# Moo_it.net
KiCad netlist of a schematic drawn in Altium Designer
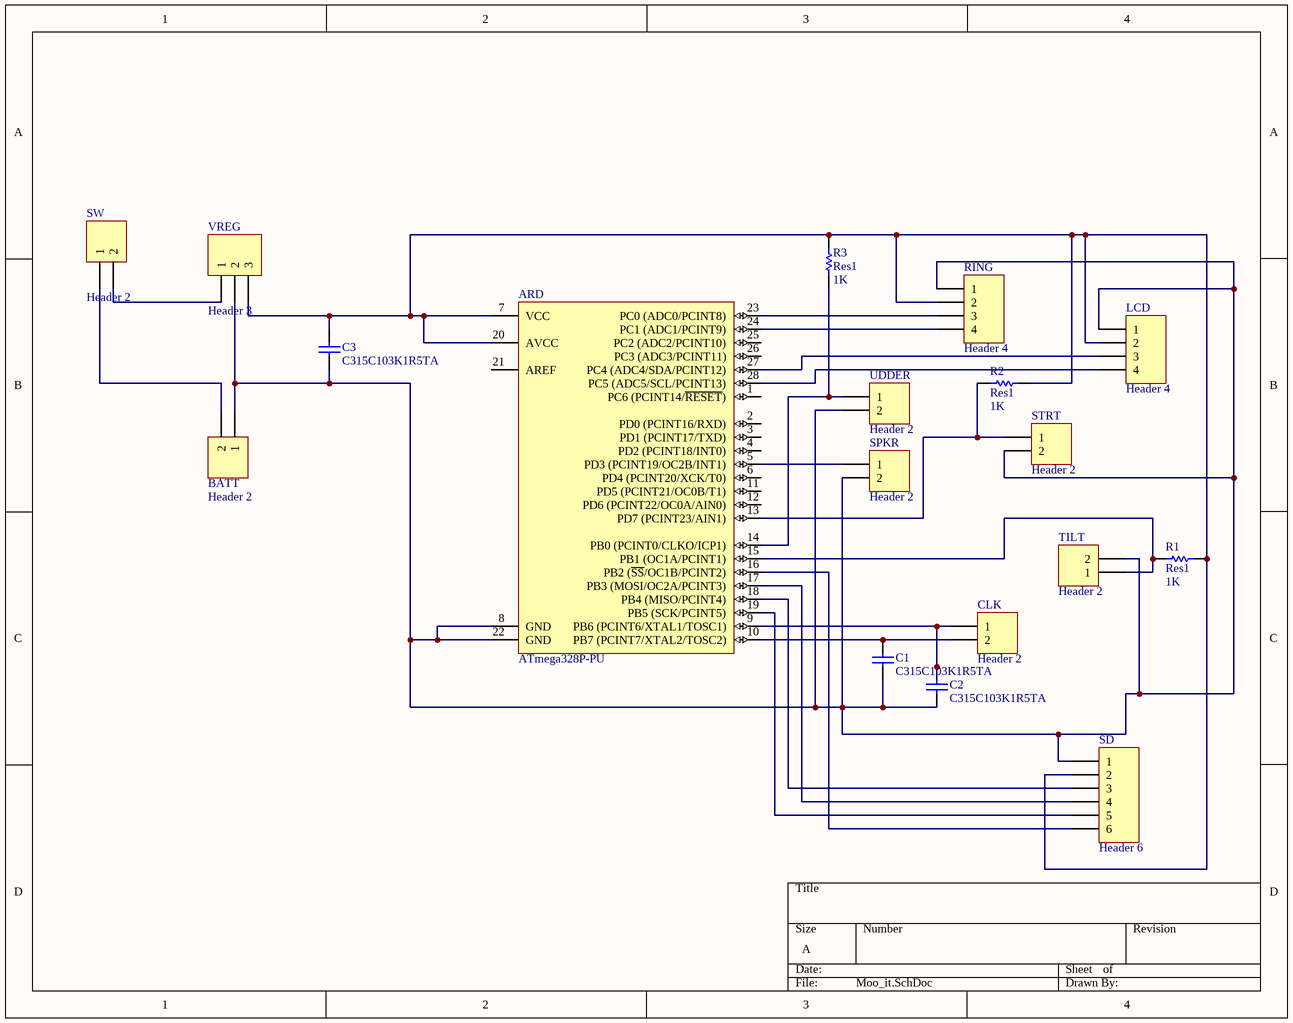
[diagram p0: Moo_it.SchDoc]

(export (version "E")
  (design (tool "Eeschema 10.0.6"))
  (components
    (comp (ref "ARD")
      (value "ATmega328P-PU")
      (footprint "28P3")
      (libsource (lib "Altium Content Vault") (part "MC-8B-ATM48-IL28"))
    )
    (comp (ref "BATT")
      (value "Header 2")
      (footprint "HDR1X2")
      (description "Header, 2-Pin")
      (fields (field (name "PUBLISHER") "Altium Limited"))
      (libsource (lib "") (part "Header 2_1"))
    )
    (comp (ref "C1")
      (value "C315C103K1R5TA")
      (footprint "KEMT-C315-THT-2")
      (description "Capacitor, Ceramic, 0.01 uF, +/- 10%, 100 V, X7R, -55 to 125 degC, 2-Pin THD, RoHS, Bulk")
      (libsource (lib "Altium Content Vault") (part "CAP-NP-2"))
    )
    (comp (ref "C2")
      (value "C315C103K1R5TA")
      (footprint "KEMT-C315-THT-2")
      (description "Capacitor, Ceramic, 0.01 uF, +/- 10%, 100 V, X7R, -55 to 125 degC, 2-Pin THD, RoHS, Bulk")
      (libsource (lib "Altium Content Vault") (part "CAP-NP-2"))
    )
    (comp (ref "C3")
      (value "C315C103K1R5TA")
      (footprint "KEMT-C315-THT-2")
      (description "Capacitor, Ceramic, 0.01 uF, +/- 10%, 100 V, X7R, -55 to 125 degC, 2-Pin THD, RoHS, Bulk")
      (libsource (lib "Altium Content Vault") (part "CAP-NP-2"))
    )
    (comp (ref "CLK")
      (value "Header 2")
      (footprint "HDR1X2")
      (description "Header, 2-Pin")
      (fields (field (name "PUBLISHER") "Altium Limited"))
      (libsource (lib "Miscellaneous Connectors") (part "Header 2"))
    )
    (comp (ref "LCD")
      (value "Header 4")
      (footprint "HDR1X4")
      (description "Header, 4-Pin")
      (fields (field (name "PUBLISHER") "Altium Limited"))
      (libsource (lib "Miscellaneous Connectors") (part "Header 4"))
    )
    (comp (ref "R1")
      (value "Res1")
      (footprint "AXIAL-0.3")
      (description "Resistor")
      (fields (field (name "ALTIUM_VALUE") "1K") (field (name "PUBLISHER") "Altium Limited"))
      (libsource (lib "Miscellaneous Devices") (part "Res1"))
    )
    (comp (ref "R2")
      (value "Res1")
      (footprint "AXIAL-0.3")
      (description "Resistor")
      (fields (field (name "ALTIUM_VALUE") "1K") (field (name "PUBLISHER") "Altium Limited"))
      (libsource (lib "Miscellaneous Devices") (part "Res1"))
    )
    (comp (ref "R3")
      (value "Res1")
      (footprint "AXIAL-0.3")
      (description "Resistor")
      (fields (field (name "ALTIUM_VALUE") "1K") (field (name "PUBLISHER") "Altium Limited"))
      (libsource (lib "Miscellaneous Devices") (part "Res1"))
    )
    (comp (ref "RING")
      (value "Header 4")
      (footprint "HDR1X4")
      (description "Header, 4-Pin")
      (fields (field (name "PUBLISHER") "Altium Limited"))
      (libsource (lib "Miscellaneous Connectors") (part "Header 4"))
    )
    (comp (ref "SD")
      (value "Header 6")
      (footprint "HDR1X6")
      (description "Header, 6-Pin")
      (fields (field (name "PUBLISHER") "Altium Limited"))
      (libsource (lib "Miscellaneous Connectors") (part "Header 6"))
    )
    (comp (ref "SPKR")
      (value "Header 2")
      (footprint "HDR1X2")
      (description "Header, 2-Pin")
      (fields (field (name "PUBLISHER") "Altium Limited"))
      (libsource (lib "Miscellaneous Connectors") (part "Header 2"))
    )
    (comp (ref "STRT")
      (value "Header 2")
      (footprint "HDR1X2")
      (description "Header, 2-Pin")
      (fields (field (name "PUBLISHER") "Altium Limited"))
      (libsource (lib "Miscellaneous Connectors") (part "Header 2"))
    )
    (comp (ref "SW")
      (value "Header 2")
      (footprint "HDR1X2")
      (description "Header, 2-Pin")
      (fields (field (name "PUBLISHER") "Altium Limited"))
      (libsource (lib "") (part "Header 2_2"))
    )
    (comp (ref "TILT")
      (value "Header 2")
      (footprint "HDR1X2")
      (description "Header, 2-Pin")
      (fields (field (name "PUBLISHER") "Altium Limited"))
      (libsource (lib "") (part "Header 2_3"))
    )
    (comp (ref "UDDER")
      (value "Header 2")
      (footprint "HDR1X2")
      (description "Header, 2-Pin")
      (fields (field (name "PUBLISHER") "Altium Limited"))
      (libsource (lib "Miscellaneous Connectors") (part "Header 2"))
    )
    (comp (ref "VREG")
      (value "Header 3")
      (footprint "HDR1X3")
      (description "Header, 3-Pin")
      (fields (field (name "PUBLISHER") "Altium Limited"))
      (libsource (lib "Miscellaneous Connectors") (part "Header 3"))
    )
  )
  (nets
    (net (code "1") (name "Net-(ARD-AVCC)") (class "Default")
      (node (ref "ARD") (pin "20") (pinfunction "AVCC_20") (pintype "power_in"))
      (node (ref "ARD") (pin "7") (pinfunction "VCC_7") (pintype "power_in"))
      (node (ref "C3") (pin "2") (pinfunction "2_2") (pintype "passive"))
      (node (ref "LCD") (pin "2") (pinfunction "2_2") (pintype "passive"))
      (node (ref "R1") (pin "2") (pinfunction "2_2") (pintype "passive"))
      (node (ref "R2") (pin "2") (pinfunction "2_2") (pintype "passive"))
      (node (ref "R3") (pin "2") (pinfunction "2_2") (pintype "passive"))
      (node (ref "RING") (pin "2") (pinfunction "2_2") (pintype "passive"))
      (node (ref "SD") (pin "2") (pinfunction "2_2") (pintype "passive"))
      (node (ref "VREG") (pin "3") (pinfunction "3_3") (pintype "passive"))
    )
    (net (code "2") (name "Net-(ARD-GND-Pad22)") (class "Default")
      (node (ref "ARD") (pin "22") (pinfunction "GND_22") (pintype "power_in"))
      (node (ref "ARD") (pin "8") (pinfunction "GND_8") (pintype "power_in"))
      (node (ref "BATT") (pin "1") (pinfunction "1_1") (pintype "passive"))
      (node (ref "C1") (pin "1") (pinfunction "1_1") (pintype "passive"))
      (node (ref "C2") (pin "1") (pinfunction "1_1") (pintype "passive"))
      (node (ref "C3") (pin "1") (pinfunction "1_1") (pintype "passive"))
      (node (ref "LCD") (pin "1") (pinfunction "1_1") (pintype "passive"))
      (node (ref "RING") (pin "1") (pinfunction "1_1") (pintype "passive"))
      (node (ref "SD") (pin "1") (pinfunction "1_1") (pintype "passive"))
      (node (ref "SPKR") (pin "2") (pinfunction "2_2") (pintype "passive"))
      (node (ref "STRT") (pin "2") (pinfunction "2_2") (pintype "passive"))
      (node (ref "TILT") (pin "2") (pinfunction "2_2") (pintype "passive"))
      (node (ref "UDDER") (pin "2") (pinfunction "2_2") (pintype "passive"))
      (node (ref "VREG") (pin "2") (pinfunction "2_2") (pintype "passive"))
    )
    (net (code "3") (name "Net-(ARD-PB0_(PCINT0{slash}CLKO{slash}ICP1))") (class "Default")
      (node (ref "ARD") (pin "14") (pinfunction "PB0_(PCINT0/CLKO/ICP1)_14") (pintype "bidirectional"))
      (node (ref "R3") (pin "1") (pinfunction "1_1") (pintype "passive"))
      (node (ref "UDDER") (pin "1") (pinfunction "1_1") (pintype "passive"))
    )
    (net (code "4") (name "Net-(ARD-PB1_(OC1A{slash}PCINT1))") (class "Default")
      (node (ref "ARD") (pin "15") (pinfunction "PB1_(OC1A/PCINT1)_15") (pintype "bidirectional"))
      (node (ref "R1") (pin "1") (pinfunction "1_1") (pintype "passive"))
      (node (ref "TILT") (pin "1") (pinfunction "1_1") (pintype "passive"))
    )
    (net (code "5") (name "Net-(ARD-PB2_(~{SS}{slash}OC1B{slash}PCINT2))") (class "Default")
      (node (ref "ARD") (pin "16") (pinfunction "PB2_(~{SS}/OC1B/PCINT2)_16") (pintype "bidirectional"))
      (node (ref "SD") (pin "6") (pinfunction "6_6") (pintype "passive"))
    )
    (net (code "6") (name "Net-(ARD-PB3_(MOSI{slash}OC2A{slash}PCINT3))") (class "Default")
      (node (ref "ARD") (pin "17") (pinfunction "PB3_(MOSI/OC2A/PCINT3)_17") (pintype "bidirectional"))
      (node (ref "SD") (pin "4") (pinfunction "4_4") (pintype "passive"))
    )
    (net (code "7") (name "Net-(ARD-PB4_(MISO{slash}PCINT4))") (class "Default")
      (node (ref "ARD") (pin "18") (pinfunction "PB4_(MISO/PCINT4)_18") (pintype "bidirectional"))
      (node (ref "SD") (pin "3") (pinfunction "3_3") (pintype "passive"))
    )
    (net (code "8") (name "Net-(ARD-PB5_(SCK{slash}PCINT5))") (class "Default")
      (node (ref "ARD") (pin "19") (pinfunction "PB5_(SCK/PCINT5)_19") (pintype "bidirectional"))
      (node (ref "SD") (pin "5") (pinfunction "5_5") (pintype "passive"))
    )
    (net (code "9") (name "Net-(ARD-PB6_(PCINT6{slash}XTAL1{slash}TOSC1))") (class "Default")
      (node (ref "ARD") (pin "9") (pinfunction "PB6_(PCINT6/XTAL1/TOSC1)_9") (pintype "bidirectional"))
      (node (ref "C2") (pin "2") (pinfunction "2_2") (pintype "passive"))
      (node (ref "CLK") (pin "1") (pinfunction "1_1") (pintype "passive"))
    )
    (net (code "10") (name "Net-(ARD-PB7_(PCINT7{slash}XTAL2{slash}TOSC2))") (class "Default")
      (node (ref "ARD") (pin "10") (pinfunction "PB7_(PCINT7/XTAL2/TOSC2)_10") (pintype "bidirectional"))
      (node (ref "C1") (pin "2") (pinfunction "2_2") (pintype "passive"))
      (node (ref "CLK") (pin "2") (pinfunction "2_2") (pintype "passive"))
    )
    (net (code "11") (name "Net-(ARD-PC0_(ADC0{slash}PCINT8))") (class "Default")
      (node (ref "ARD") (pin "23") (pinfunction "PC0_(ADC0/PCINT8)_23") (pintype "bidirectional"))
      (node (ref "RING") (pin "3") (pinfunction "3_3") (pintype "passive"))
    )
    (net (code "12") (name "Net-(ARD-PC1_(ADC1{slash}PCINT9))") (class "Default")
      (node (ref "ARD") (pin "24") (pinfunction "PC1_(ADC1/PCINT9)_24") (pintype "bidirectional"))
      (node (ref "RING") (pin "4") (pinfunction "4_4") (pintype "passive"))
    )
    (net (code "13") (name "Net-(ARD-PC4_(ADC4{slash}SDA{slash}PCINT12))") (class "Default")
      (node (ref "ARD") (pin "27") (pinfunction "PC4_(ADC4/SDA/PCINT12)_27") (pintype "bidirectional"))
      (node (ref "LCD") (pin "3") (pinfunction "3_3") (pintype "passive"))
    )
    (net (code "14") (name "Net-(ARD-PC5_(ADC5{slash}SCL{slash}PCINT13))") (class "Default")
      (node (ref "ARD") (pin "28") (pinfunction "PC5_(ADC5/SCL/PCINT13)_28") (pintype "bidirectional"))
      (node (ref "LCD") (pin "4") (pinfunction "4_4") (pintype "passive"))
    )
    (net (code "15") (name "Net-(ARD-PD3_(PCINT19{slash}OC2B{slash}INT1))") (class "Default")
      (node (ref "ARD") (pin "5") (pinfunction "PD3_(PCINT19/OC2B/INT1)_5") (pintype "bidirectional"))
      (node (ref "SPKR") (pin "1") (pinfunction "1_1") (pintype "passive"))
    )
    (net (code "16") (name "Net-(ARD-PD7_(PCINT23{slash}AIN1))") (class "Default")
      (node (ref "ARD") (pin "13") (pinfunction "PD7_(PCINT23/AIN1)_13") (pintype "bidirectional"))
      (node (ref "R2") (pin "1") (pinfunction "1_1") (pintype "passive"))
      (node (ref "STRT") (pin "1") (pinfunction "1_1") (pintype "passive"))
    )
    (net (code "17") (name "Net-(BATT-Pad2)") (class "Default")
      (node (ref "BATT") (pin "2") (pinfunction "2_2") (pintype "passive"))
      (node (ref "SW") (pin "1") (pinfunction "1_1") (pintype "passive"))
    )
    (net (code "18") (name "Net-(SW-Pad2)") (class "Default")
      (node (ref "SW") (pin "2") (pinfunction "2_2") (pintype "passive"))
      (node (ref "VREG") (pin "1") (pinfunction "1_1") (pintype "passive"))
    )
    (net (code "19") (name "unconnected-(ARD-AREF-Pad21)") (class "Default")
      (node (ref "ARD") (pin "21") (pinfunction "AREF_21") (pintype "power_in"))
    )
    (net (code "20") (name "unconnected-(ARD-PC2_(ADC2{slash}PCINT10)-Pad25)") (class "Default")
      (node (ref "ARD") (pin "25") (pinfunction "PC2_(ADC2/PCINT10)_25") (pintype "bidirectional"))
    )
    (net (code "21") (name "unconnected-(ARD-PC3_(ADC3{slash}PCINT11)-Pad26)") (class "Default")
      (node (ref "ARD") (pin "26") (pinfunction "PC3_(ADC3/PCINT11)_26") (pintype "bidirectional"))
    )
    (net (code "22") (name "unconnected-(ARD-PC6_(PCINT14{slash}~{RESET})-Pad1)") (class "Default")
      (node (ref "ARD") (pin "1") (pinfunction "PC6_(PCINT14/~{RESET})_1") (pintype "bidirectional"))
    )
    (net (code "23") (name "unconnected-(ARD-PD0_(PCINT16{slash}RXD)-Pad2)") (class "Default")
      (node (ref "ARD") (pin "2") (pinfunction "PD0_(PCINT16/RXD)_2") (pintype "bidirectional"))
    )
    (net (code "24") (name "unconnected-(ARD-PD1_(PCINT17{slash}TXD)-Pad3)") (class "Default")
      (node (ref "ARD") (pin "3") (pinfunction "PD1_(PCINT17/TXD)_3") (pintype "bidirectional"))
    )
    (net (code "25") (name "unconnected-(ARD-PD2_(PCINT18{slash}INT0)-Pad4)") (class "Default")
      (node (ref "ARD") (pin "4") (pinfunction "PD2_(PCINT18/INT0)_4") (pintype "bidirectional"))
    )
    (net (code "26") (name "unconnected-(ARD-PD4_(PCINT20{slash}XCK{slash}T0)-Pad6)") (class "Default")
      (node (ref "ARD") (pin "6") (pinfunction "PD4_(PCINT20/XCK/T0)_6") (pintype "bidirectional"))
    )
    (net (code "27") (name "unconnected-(ARD-PD5_(PCINT21{slash}OC0B{slash}T1)-Pad11)") (class "Default")
      (node (ref "ARD") (pin "11") (pinfunction "PD5_(PCINT21/OC0B/T1)_11") (pintype "bidirectional"))
    )
    (net (code "28") (name "unconnected-(ARD-PD6_(PCINT22{slash}OC0A{slash}AIN0)-Pad12)") (class "Default")
      (node (ref "ARD") (pin "12") (pinfunction "PD6_(PCINT22/OC0A/AIN0)_12") (pintype "bidirectional"))
    )
  )
)
